# LTC2320-16.net
KiCad netlist of a schematic drawn in Altium Designer
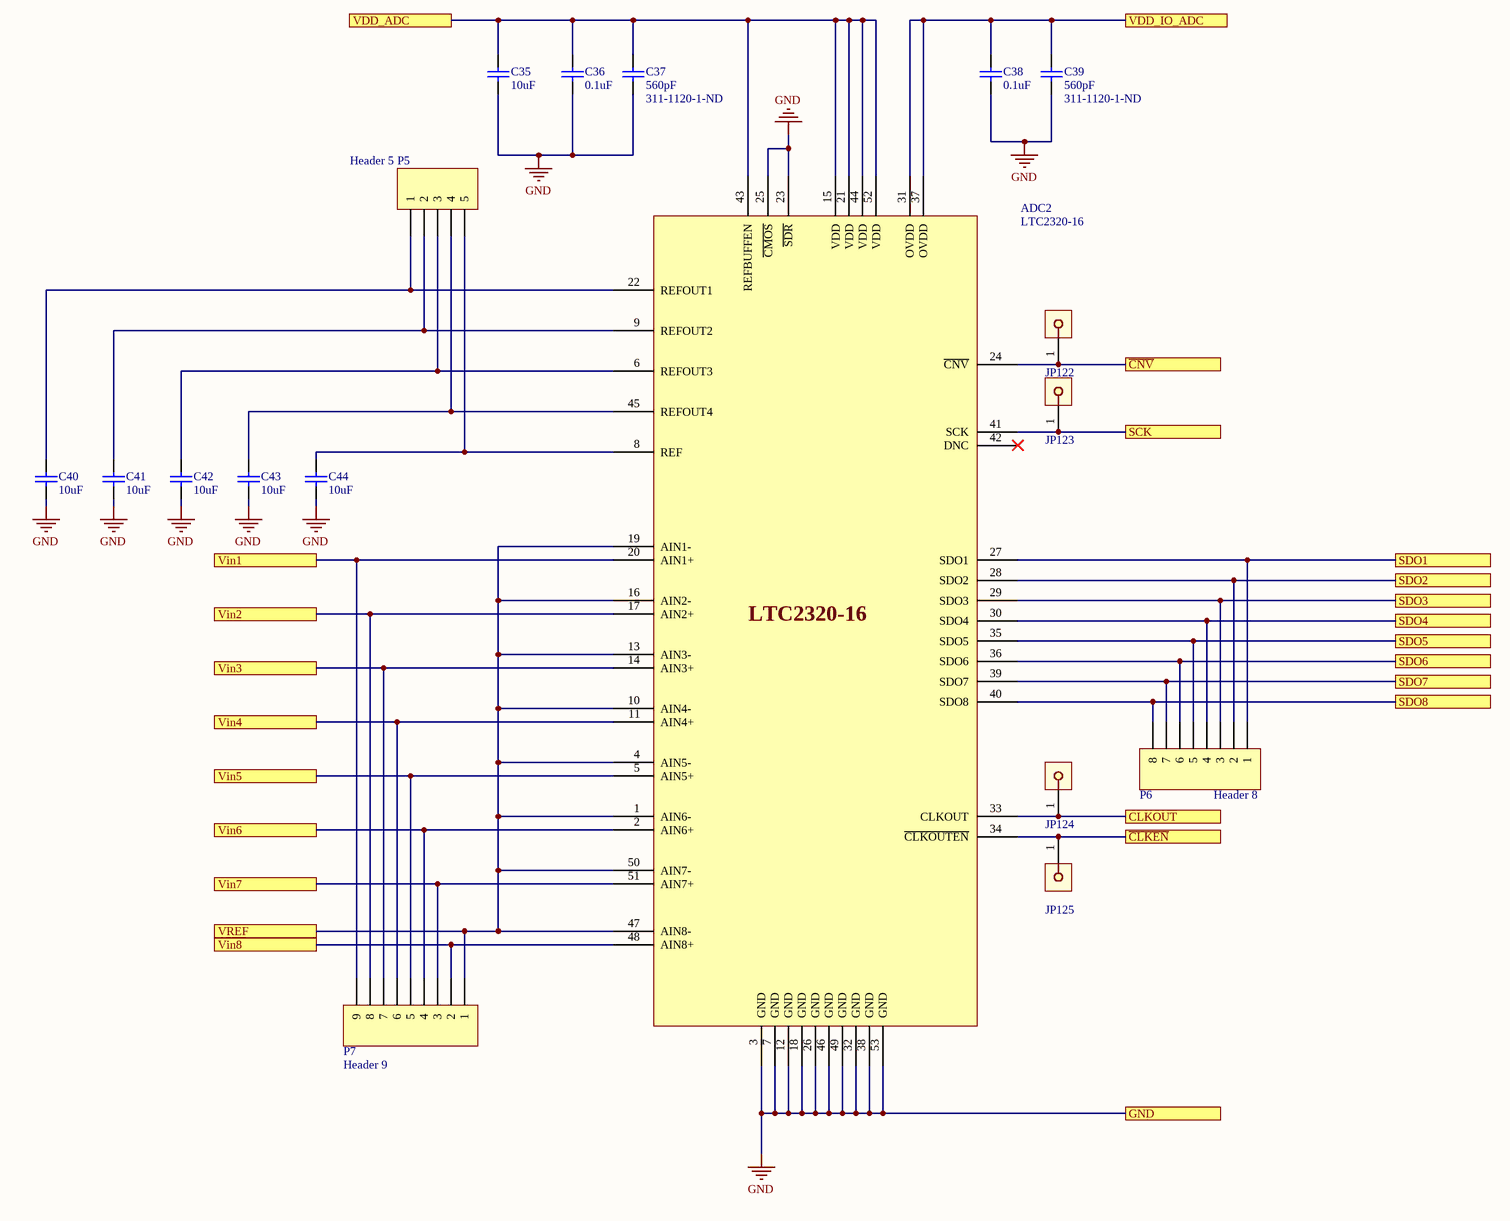
[diagram p0: LTC2320-16.SchDoc]

(export (version "E")
  (design (tool "Eeschema 10.0.6"))
  (components
    (comp (ref "ADC2")
      (value "LTC2320-16")
      (footprint "LTC2320HUKG")
      (description "Octal, 16-Bit, 1.5Msps/Ch Simultaneous Sampling ADC")
      (libsource (lib "Chip1_TestBoard") (part "LTC2320-16"))
    )
    (comp (ref "C35")
      (value "10uF")
      (footprint "CLS_Library:C0805")
      (description "Cap 10uF")
      (fields
        (field (name "MANUFACTURER") "Taiyo Yuden")
        (field (name "MANUFACTURER PART NUMBER") "UMK212SD103KD-T")
      )
      (libsource (lib "Chip1_TestBoard") (part "Cap 10uF"))
    )
    (comp (ref "C36")
      (value "0.1uF")
      (footprint "CLS_Library:C0805")
      (description "Cap 0.1uF")
      (fields
        (field (name "MANUFACTURER") "Taiyo Yuden")
        (field (name "MANUFACTURER PART NUMBER") "UMK212SD103KD-T")
      )
      (libsource (lib "Chip1_TestBoard") (part "Cap 0.1uF"))
    )
    (comp (ref "C37")
      (value "560pF")
      (footprint "CLS_Library:C0805")
      (description "Cap 560pF")
      (fields
        (field (name "MANUFACTURER") "Taiyo Yuden")
        (field (name "MANUFACTURER PART NUMBER") "UMK212SD103KD-T")
        (field (name "SUPPLIER PART NUMBER 1") "311-1120-1-ND")
      )
      (libsource (lib "Chip1_TestBoard") (part "Cap 560pF"))
    )
    (comp (ref "C38")
      (value "0.1uF")
      (footprint "CLS_Library:C0805")
      (description "Cap 0.1uF")
      (fields
        (field (name "MANUFACTURER") "Taiyo Yuden")
        (field (name "MANUFACTURER PART NUMBER") "UMK212SD103KD-T")
      )
      (libsource (lib "Chip1_TestBoard") (part "Cap 0.1uF"))
    )
    (comp (ref "C39")
      (value "560pF")
      (footprint "CLS_Library:C0805")
      (description "Cap 560pF")
      (fields
        (field (name "MANUFACTURER") "Taiyo Yuden")
        (field (name "MANUFACTURER PART NUMBER") "UMK212SD103KD-T")
        (field (name "SUPPLIER PART NUMBER 1") "311-1120-1-ND")
      )
      (libsource (lib "Chip1_TestBoard") (part "Cap 560pF"))
    )
    (comp (ref "C40")
      (value "10uF")
      (footprint "CLS_Library:C0805")
      (description "Cap 10uF")
      (fields
        (field (name "MANUFACTURER") "Taiyo Yuden")
        (field (name "MANUFACTURER PART NUMBER") "UMK212SD103KD-T")
      )
      (libsource (lib "Chip1_TestBoard") (part "Cap 10uF"))
    )
    (comp (ref "C41")
      (value "10uF")
      (footprint "CLS_Library:C0805")
      (description "Cap 10uF")
      (fields
        (field (name "MANUFACTURER") "Taiyo Yuden")
        (field (name "MANUFACTURER PART NUMBER") "UMK212SD103KD-T")
      )
      (libsource (lib "Chip1_TestBoard") (part "Cap 10uF"))
    )
    (comp (ref "C42")
      (value "10uF")
      (footprint "CLS_Library:C0805")
      (description "Cap 10uF")
      (fields
        (field (name "MANUFACTURER") "Taiyo Yuden")
        (field (name "MANUFACTURER PART NUMBER") "UMK212SD103KD-T")
      )
      (libsource (lib "Chip1_TestBoard") (part "Cap 10uF"))
    )
    (comp (ref "C43")
      (value "10uF")
      (footprint "CLS_Library:C0805")
      (description "Cap 10uF")
      (fields
        (field (name "MANUFACTURER") "Taiyo Yuden")
        (field (name "MANUFACTURER PART NUMBER") "UMK212SD103KD-T")
      )
      (libsource (lib "Chip1_TestBoard") (part "Cap 10uF"))
    )
    (comp (ref "C44")
      (value "10uF")
      (footprint "CLS_Library:C0805")
      (description "Cap 10uF")
      (fields
        (field (name "MANUFACTURER") "Taiyo Yuden")
        (field (name "MANUFACTURER PART NUMBER") "UMK212SD103KD-T")
      )
      (libsource (lib "Chip1_TestBoard") (part "Cap 10uF"))
    )
    (comp (ref "JP122")
      (value "01x01")
      (footprint "01x01_0_0.1in_th_straight_b_nom")
      (description "01X01 generic terminal connector")
      (libsource (lib "Chip1_TestBoard") (part "01x01"))
    )
    (comp (ref "JP123")
      (value "01x01")
      (footprint "01x01_0_0.1in_th_straight_b_nom")
      (description "01X01 generic terminal connector")
      (libsource (lib "Chip1_TestBoard") (part "01x01"))
    )
    (comp (ref "JP124")
      (value "01x01")
      (footprint "01x01_0_0.1in_th_straight_b_nom")
      (description "01X01 generic terminal connector")
      (libsource (lib "Chip1_TestBoard") (part "01x01"))
    )
    (comp (ref "JP125")
      (value "01x01")
      (footprint "01x01_0_0.1in_th_straight_b_nom")
      (description "01X01 generic terminal connector")
      (libsource (lib "") (part "01x01_1"))
    )
    (comp (ref "P5")
      (value "Header 5")
      (footprint "HDR1X5")
      (description "Header, 5-Pin")
      (fields (field (name "PUBLISHER") "Altium Limited"))
      (libsource (lib "Miscellaneous Connectors") (part "Header 5"))
    )
    (comp (ref "P6")
      (value "Header 8")
      (footprint "HDR1X8")
      (description "Header, 8-Pin")
      (fields (field (name "PUBLISHER") "Altium Limited"))
      (libsource (lib "Miscellaneous Connectors") (part "Header 8"))
    )
    (comp (ref "P7")
      (value "Header 9")
      (footprint "HDR1X9")
      (description "Header, 9-Pin")
      (fields (field (name "PUBLISHER") "Altium Limited"))
      (libsource (lib "Miscellaneous Connectors") (part "Header 9"))
    )
  )
  (nets
    (net (code "1") (name "/CLKOUT") (class "Default")
      (node (ref "ADC2") (pin "33") (pinfunction "CLKOUT_33") (pintype "passive"))
      (node (ref "JP124") (pin "1") (pinfunction "1_1") (pintype "passive"))
    )
    (net (code "2") (name "/SCK") (class "Default")
      (node (ref "ADC2") (pin "41") (pinfunction "SCK_41") (pintype "passive"))
      (node (ref "JP123") (pin "1") (pinfunction "1_1") (pintype "passive"))
    )
    (net (code "3") (name "/SDO1") (class "Default")
      (node (ref "ADC2") (pin "27") (pinfunction "SDO1_27") (pintype "passive"))
      (node (ref "P6") (pin "1") (pinfunction "1_1") (pintype "passive"))
    )
    (net (code "4") (name "/SDO2") (class "Default")
      (node (ref "ADC2") (pin "28") (pinfunction "SDO2_28") (pintype "passive"))
      (node (ref "P6") (pin "2") (pinfunction "2_2") (pintype "passive"))
    )
    (net (code "5") (name "/SDO3") (class "Default")
      (node (ref "ADC2") (pin "29") (pinfunction "SDO3_29") (pintype "passive"))
      (node (ref "P6") (pin "3") (pinfunction "3_3") (pintype "passive"))
    )
    (net (code "6") (name "/SDO4") (class "Default")
      (node (ref "ADC2") (pin "30") (pinfunction "SDO4_30") (pintype "passive"))
      (node (ref "P6") (pin "4") (pinfunction "4_4") (pintype "passive"))
    )
    (net (code "7") (name "/SDO5") (class "Default")
      (node (ref "ADC2") (pin "35") (pinfunction "SDO5_35") (pintype "passive"))
      (node (ref "P6") (pin "5") (pinfunction "5_5") (pintype "passive"))
    )
    (net (code "8") (name "/SDO6") (class "Default")
      (node (ref "ADC2") (pin "36") (pinfunction "SDO6_36") (pintype "passive"))
      (node (ref "P6") (pin "6") (pinfunction "6_6") (pintype "passive"))
    )
    (net (code "9") (name "/SDO7") (class "Default")
      (node (ref "ADC2") (pin "39") (pinfunction "SDO7_39") (pintype "passive"))
      (node (ref "P6") (pin "7") (pinfunction "7_7") (pintype "passive"))
    )
    (net (code "10") (name "/SDO8") (class "Default")
      (node (ref "ADC2") (pin "40") (pinfunction "SDO8_40") (pintype "passive"))
      (node (ref "P6") (pin "8") (pinfunction "8_8") (pintype "passive"))
    )
    (net (code "11") (name "/VDD_ADC") (class "Default")
      (node (ref "ADC2") (pin "15") (pinfunction "VDD_15") (pintype "passive"))
      (node (ref "ADC2") (pin "21") (pinfunction "VDD_21") (pintype "passive"))
      (node (ref "ADC2") (pin "43") (pinfunction "REFBUFFEN_43") (pintype "passive"))
      (node (ref "ADC2") (pin "44") (pinfunction "VDD_44") (pintype "passive"))
      (node (ref "ADC2") (pin "52") (pinfunction "VDD_52") (pintype "passive"))
      (node (ref "C35") (pin "2") (pinfunction "2_2") (pintype "passive"))
      (node (ref "C36") (pin "2") (pinfunction "2_2") (pintype "passive"))
      (node (ref "C37") (pin "2") (pinfunction "2_2") (pintype "passive"))
    )
    (net (code "12") (name "/VDD_IO_ADC") (class "Default")
      (node (ref "ADC2") (pin "31") (pinfunction "OVDD_31") (pintype "passive"))
      (node (ref "ADC2") (pin "37") (pinfunction "OVDD_37") (pintype "passive"))
      (node (ref "C38") (pin "2") (pinfunction "2_2") (pintype "passive"))
      (node (ref "C39") (pin "2") (pinfunction "2_2") (pintype "passive"))
    )
    (net (code "13") (name "/VREF") (class "Default")
      (node (ref "ADC2") (pin "1") (pinfunction "AIN6-_1") (pintype "passive"))
      (node (ref "ADC2") (pin "10") (pinfunction "AIN4-_10") (pintype "passive"))
      (node (ref "ADC2") (pin "13") (pinfunction "AIN3-_13") (pintype "passive"))
      (node (ref "ADC2") (pin "16") (pinfunction "AIN2-_16") (pintype "passive"))
      (node (ref "ADC2") (pin "19") (pinfunction "AIN1-_19") (pintype "passive"))
      (node (ref "ADC2") (pin "4") (pinfunction "AIN5-_4") (pintype "passive"))
      (node (ref "ADC2") (pin "47") (pinfunction "AIN8-_47") (pintype "passive"))
      (node (ref "ADC2") (pin "50") (pinfunction "AIN7-_50") (pintype "passive"))
      (node (ref "P7") (pin "1") (pinfunction "1_1") (pintype "passive"))
    )
    (net (code "14") (name "/Vin1") (class "Default")
      (node (ref "ADC2") (pin "20") (pinfunction "AIN1+_20") (pintype "passive"))
      (node (ref "P7") (pin "9") (pinfunction "9_9") (pintype "passive"))
    )
    (net (code "15") (name "/Vin2") (class "Default")
      (node (ref "ADC2") (pin "17") (pinfunction "AIN2+_17") (pintype "passive"))
      (node (ref "P7") (pin "8") (pinfunction "8_8") (pintype "passive"))
    )
    (net (code "16") (name "/Vin3") (class "Default")
      (node (ref "ADC2") (pin "14") (pinfunction "AIN3+_14") (pintype "passive"))
      (node (ref "P7") (pin "7") (pinfunction "7_7") (pintype "passive"))
    )
    (net (code "17") (name "/Vin4") (class "Default")
      (node (ref "ADC2") (pin "11") (pinfunction "AIN4+_11") (pintype "passive"))
      (node (ref "P7") (pin "6") (pinfunction "6_6") (pintype "passive"))
    )
    (net (code "18") (name "/Vin5") (class "Default")
      (node (ref "ADC2") (pin "5") (pinfunction "AIN5+_5") (pintype "passive"))
      (node (ref "P7") (pin "5") (pinfunction "5_5") (pintype "passive"))
    )
    (net (code "19") (name "/Vin6") (class "Default")
      (node (ref "ADC2") (pin "2") (pinfunction "AIN6+_2") (pintype "passive"))
      (node (ref "P7") (pin "4") (pinfunction "4_4") (pintype "passive"))
    )
    (net (code "20") (name "/Vin7") (class "Default")
      (node (ref "ADC2") (pin "51") (pinfunction "AIN7+_51") (pintype "passive"))
      (node (ref "P7") (pin "3") (pinfunction "3_3") (pintype "passive"))
    )
    (net (code "21") (name "/Vin8") (class "Default")
      (node (ref "ADC2") (pin "48") (pinfunction "AIN8+_48") (pintype "passive"))
      (node (ref "P7") (pin "2") (pinfunction "2_2") (pintype "passive"))
    )
    (net (code "22") (name "/~{CLKEN}") (class "Default")
      (node (ref "ADC2") (pin "34") (pinfunction "~{CLKOUTEN}_34") (pintype "passive"))
      (node (ref "JP125") (pin "1") (pinfunction "1_1") (pintype "passive"))
    )
    (net (code "23") (name "/~{CNV}") (class "Default")
      (node (ref "ADC2") (pin "24") (pinfunction "~{CNV}_24") (pintype "passive"))
      (node (ref "JP122") (pin "1") (pinfunction "1_1") (pintype "passive"))
    )
    (net (code "24") (name "GND") (class "Default")
      (node (ref "ADC2") (pin "12") (pinfunction "GND_12") (pintype "passive"))
      (node (ref "ADC2") (pin "18") (pinfunction "GND_18") (pintype "passive"))
      (node (ref "ADC2") (pin "23") (pinfunction "~{SDR}_23") (pintype "passive"))
      (node (ref "ADC2") (pin "25") (pinfunction "~{CMOS}_25") (pintype "passive"))
      (node (ref "ADC2") (pin "26") (pinfunction "GND_26") (pintype "passive"))
      (node (ref "ADC2") (pin "3") (pinfunction "GND_3") (pintype "passive"))
      (node (ref "ADC2") (pin "32") (pinfunction "GND_32") (pintype "passive"))
      (node (ref "ADC2") (pin "38") (pinfunction "GND_38") (pintype "passive"))
      (node (ref "ADC2") (pin "46") (pinfunction "GND_46") (pintype "passive"))
      (node (ref "ADC2") (pin "49") (pinfunction "GND_49") (pintype "passive"))
      (node (ref "ADC2") (pin "53") (pinfunction "GND_53") (pintype "passive"))
      (node (ref "ADC2") (pin "7") (pinfunction "GND_7") (pintype "passive"))
      (node (ref "C35") (pin "1") (pinfunction "1_1") (pintype "passive"))
      (node (ref "C36") (pin "1") (pinfunction "1_1") (pintype "passive"))
      (node (ref "C37") (pin "1") (pinfunction "1_1") (pintype "passive"))
      (node (ref "C38") (pin "1") (pinfunction "1_1") (pintype "passive"))
      (node (ref "C39") (pin "1") (pinfunction "1_1") (pintype "passive"))
      (node (ref "C40") (pin "1") (pinfunction "1_1") (pintype "passive"))
      (node (ref "C41") (pin "1") (pinfunction "1_1") (pintype "passive"))
      (node (ref "C42") (pin "1") (pinfunction "1_1") (pintype "passive"))
      (node (ref "C43") (pin "1") (pinfunction "1_1") (pintype "passive"))
      (node (ref "C44") (pin "1") (pinfunction "1_1") (pintype "passive"))
    )
    (net (code "25") (name "Net-(ADC2-REF)") (class "Default")
      (node (ref "ADC2") (pin "8") (pinfunction "REF_8") (pintype "passive"))
      (node (ref "C44") (pin "2") (pinfunction "2_2") (pintype "passive"))
      (node (ref "P5") (pin "5") (pinfunction "5_5") (pintype "passive"))
    )
    (net (code "26") (name "Net-(ADC2-REFOUT1)") (class "Default")
      (node (ref "ADC2") (pin "22") (pinfunction "REFOUT1_22") (pintype "passive"))
      (node (ref "C40") (pin "2") (pinfunction "2_2") (pintype "passive"))
      (node (ref "P5") (pin "1") (pinfunction "1_1") (pintype "passive"))
    )
    (net (code "27") (name "Net-(ADC2-REFOUT2)") (class "Default")
      (node (ref "ADC2") (pin "9") (pinfunction "REFOUT2_9") (pintype "passive"))
      (node (ref "C41") (pin "2") (pinfunction "2_2") (pintype "passive"))
      (node (ref "P5") (pin "2") (pinfunction "2_2") (pintype "passive"))
    )
    (net (code "28") (name "Net-(ADC2-REFOUT3)") (class "Default")
      (node (ref "ADC2") (pin "6") (pinfunction "REFOUT3_6") (pintype "passive"))
      (node (ref "C42") (pin "2") (pinfunction "2_2") (pintype "passive"))
      (node (ref "P5") (pin "3") (pinfunction "3_3") (pintype "passive"))
    )
    (net (code "29") (name "Net-(ADC2-REFOUT4)") (class "Default")
      (node (ref "ADC2") (pin "45") (pinfunction "REFOUT4_45") (pintype "passive"))
      (node (ref "C43") (pin "2") (pinfunction "2_2") (pintype "passive"))
      (node (ref "P5") (pin "4") (pinfunction "4_4") (pintype "passive"))
    )
    (net (code "30") (name "unconnected-(ADC2-DNC-Pad42)") (class "Default")
      (node (ref "ADC2") (pin "42") (pinfunction "DNC_42") (pintype "passive+no_connect"))
    )
  )
)
